# arduino_mega_shield.net
KiCad netlist of a schematic drawn in EAGLE
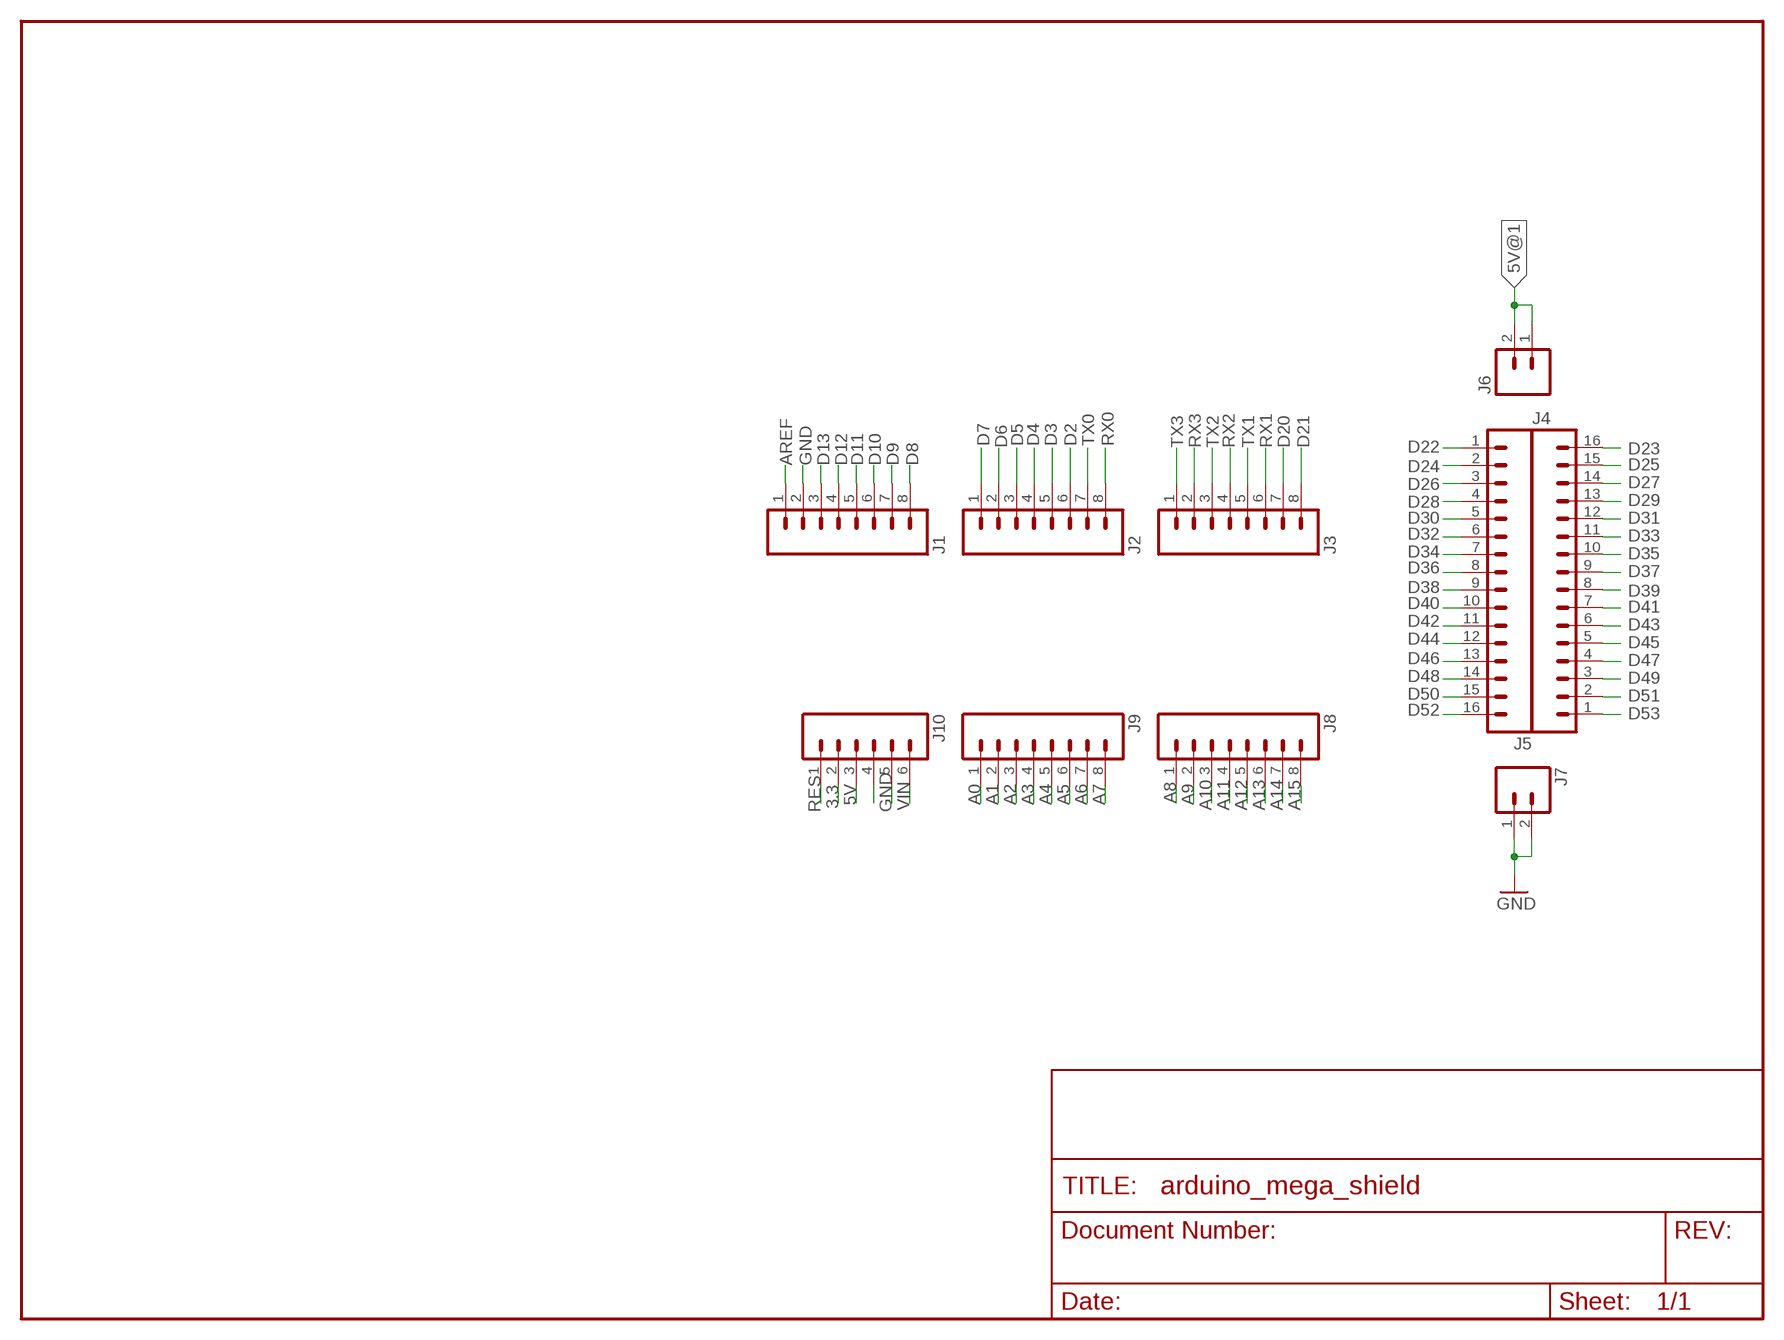
[diagram p0: schematic, sheet 1]

(export (version "E")
  (design (tool "Eeschema 10.0.6"))
  (components
    (comp (ref "J1")
      (value "M08LONGPADS")
      (footprint "eagle-import:1X08_LONGPADS")
      (libsource (lib "eagle-import") (part "M08LONGPADS"))
    )
    (comp (ref "J2")
      (value "M08LONGPADS")
      (footprint "eagle-import:1X08_LONGPADS")
      (libsource (lib "eagle-import") (part "M08LONGPADS"))
    )
    (comp (ref "J3")
      (value "M08LONGPADS")
      (footprint "eagle-import:1X08_LONGPADS")
      (libsource (lib "eagle-import") (part "M08LONGPADS"))
    )
    (comp (ref "J4")
      (value "M16PTH")
      (footprint "eagle-import:1X16")
      (libsource (lib "eagle-import") (part "M16PTH"))
    )
    (comp (ref "J5")
      (value "M16PTH")
      (footprint "eagle-import:1X16")
      (libsource (lib "eagle-import") (part "M16PTH"))
    )
    (comp (ref "J6")
      (value "M02PTH")
      (footprint "eagle-import:1X02")
      (libsource (lib "eagle-import") (part "M02PTH"))
    )
    (comp (ref "J7")
      (value "M02PTH")
      (footprint "eagle-import:1X02")
      (libsource (lib "eagle-import") (part "M02PTH"))
    )
    (comp (ref "J8")
      (value "M08LONGPADS")
      (footprint "eagle-import:1X08_LONGPADS")
      (libsource (lib "eagle-import") (part "M08LONGPADS"))
    )
    (comp (ref "J9")
      (value "M08LONGPADS")
      (footprint "eagle-import:1X08_LONGPADS")
      (libsource (lib "eagle-import") (part "M08LONGPADS"))
    )
    (comp (ref "J10")
      (value "M06LONGPADS")
      (footprint "eagle-import:1X06_LONGPADS")
      (libsource (lib "eagle-import") (part "M06LONGPADS"))
    )
  )
  (nets
    (net (code "1") (name "/3.3") (class "Default")
      (node (ref "J10") (pin "2") (pinfunction "2_2") (pintype "passive"))
    )
    (net (code "2") (name "/5V") (class "Default")
      (node (ref "J10") (pin "3") (pinfunction "3_3") (pintype "passive"))
    )
    (net (code "3") (name "/A0") (class "Default")
      (node (ref "J9") (pin "1") (pinfunction "1_1") (pintype "passive"))
    )
    (net (code "4") (name "/A1") (class "Default")
      (node (ref "J9") (pin "2") (pinfunction "2_2") (pintype "passive"))
    )
    (net (code "5") (name "/A2") (class "Default")
      (node (ref "J9") (pin "3") (pinfunction "3_3") (pintype "passive"))
    )
    (net (code "6") (name "/A3") (class "Default")
      (node (ref "J9") (pin "4") (pinfunction "4_4") (pintype "passive"))
    )
    (net (code "7") (name "/A4") (class "Default")
      (node (ref "J9") (pin "5") (pinfunction "5_5") (pintype "passive"))
    )
    (net (code "8") (name "/A5") (class "Default")
      (node (ref "J9") (pin "6") (pinfunction "6_6") (pintype "passive"))
    )
    (net (code "9") (name "/A6") (class "Default")
      (node (ref "J9") (pin "7") (pinfunction "7_7") (pintype "passive"))
    )
    (net (code "10") (name "/A7") (class "Default")
      (node (ref "J9") (pin "8") (pinfunction "8_8") (pintype "passive"))
    )
    (net (code "11") (name "/A8") (class "Default")
      (node (ref "J8") (pin "1") (pinfunction "1_1") (pintype "passive"))
    )
    (net (code "12") (name "/A9") (class "Default")
      (node (ref "J8") (pin "2") (pinfunction "2_2") (pintype "passive"))
    )
    (net (code "13") (name "/A10") (class "Default")
      (node (ref "J8") (pin "3") (pinfunction "3_3") (pintype "passive"))
    )
    (net (code "14") (name "/A11") (class "Default")
      (node (ref "J8") (pin "4") (pinfunction "4_4") (pintype "passive"))
    )
    (net (code "15") (name "/A12") (class "Default")
      (node (ref "J8") (pin "5") (pinfunction "5_5") (pintype "passive"))
    )
    (net (code "16") (name "/A13") (class "Default")
      (node (ref "J8") (pin "6") (pinfunction "6_6") (pintype "passive"))
    )
    (net (code "17") (name "/A14") (class "Default")
      (node (ref "J8") (pin "7") (pinfunction "7_7") (pintype "passive"))
    )
    (net (code "18") (name "/A15") (class "Default")
      (node (ref "J8") (pin "8") (pinfunction "8_8") (pintype "passive"))
    )
    (net (code "19") (name "/AREF") (class "Default")
      (node (ref "J1") (pin "1") (pinfunction "1_1") (pintype "passive"))
    )
    (net (code "20") (name "/D2") (class "Default")
      (node (ref "J2") (pin "6") (pinfunction "6_6") (pintype "passive"))
    )
    (net (code "21") (name "/D3") (class "Default")
      (node (ref "J2") (pin "5") (pinfunction "5_5") (pintype "passive"))
    )
    (net (code "22") (name "/D4") (class "Default")
      (node (ref "J2") (pin "4") (pinfunction "4_4") (pintype "passive"))
    )
    (net (code "23") (name "/D5") (class "Default")
      (node (ref "J2") (pin "3") (pinfunction "3_3") (pintype "passive"))
    )
    (net (code "24") (name "/D6") (class "Default")
      (node (ref "J2") (pin "2") (pinfunction "2_2") (pintype "passive"))
    )
    (net (code "25") (name "/D7") (class "Default")
      (node (ref "J2") (pin "1") (pinfunction "1_1") (pintype "passive"))
    )
    (net (code "26") (name "/D8") (class "Default")
      (node (ref "J1") (pin "8") (pinfunction "8_8") (pintype "passive"))
    )
    (net (code "27") (name "/D9") (class "Default")
      (node (ref "J1") (pin "7") (pinfunction "7_7") (pintype "passive"))
    )
    (net (code "28") (name "/D10") (class "Default")
      (node (ref "J1") (pin "6") (pinfunction "6_6") (pintype "passive"))
    )
    (net (code "29") (name "/D11") (class "Default")
      (node (ref "J1") (pin "5") (pinfunction "5_5") (pintype "passive"))
    )
    (net (code "30") (name "/D12") (class "Default")
      (node (ref "J1") (pin "4") (pinfunction "4_4") (pintype "passive"))
    )
    (net (code "31") (name "/D13") (class "Default")
      (node (ref "J1") (pin "3") (pinfunction "3_3") (pintype "passive"))
    )
    (net (code "32") (name "/D20") (class "Default")
      (node (ref "J3") (pin "7") (pinfunction "7_7") (pintype "passive"))
    )
    (net (code "33") (name "/D21") (class "Default")
      (node (ref "J3") (pin "8") (pinfunction "8_8") (pintype "passive"))
    )
    (net (code "34") (name "/D22") (class "Default")
      (node (ref "J5") (pin "1") (pinfunction "1_1") (pintype "passive"))
    )
    (net (code "35") (name "/D23") (class "Default")
      (node (ref "J4") (pin "16") (pinfunction "16_16") (pintype "passive"))
    )
    (net (code "36") (name "/D24") (class "Default")
      (node (ref "J5") (pin "2") (pinfunction "2_2") (pintype "passive"))
    )
    (net (code "37") (name "/D25") (class "Default")
      (node (ref "J4") (pin "15") (pinfunction "15_15") (pintype "passive"))
    )
    (net (code "38") (name "/D26") (class "Default")
      (node (ref "J5") (pin "3") (pinfunction "3_3") (pintype "passive"))
    )
    (net (code "39") (name "/D27") (class "Default")
      (node (ref "J4") (pin "14") (pinfunction "14_14") (pintype "passive"))
    )
    (net (code "40") (name "/D28") (class "Default")
      (node (ref "J5") (pin "4") (pinfunction "4_4") (pintype "passive"))
    )
    (net (code "41") (name "/D29") (class "Default")
      (node (ref "J4") (pin "13") (pinfunction "13_13") (pintype "passive"))
    )
    (net (code "42") (name "/D30") (class "Default")
      (node (ref "J5") (pin "5") (pinfunction "5_5") (pintype "passive"))
    )
    (net (code "43") (name "/D31") (class "Default")
      (node (ref "J4") (pin "12") (pinfunction "12_12") (pintype "passive"))
    )
    (net (code "44") (name "/D32") (class "Default")
      (node (ref "J5") (pin "6") (pinfunction "6_6") (pintype "passive"))
    )
    (net (code "45") (name "/D33") (class "Default")
      (node (ref "J4") (pin "11") (pinfunction "11_11") (pintype "passive"))
    )
    (net (code "46") (name "/D34") (class "Default")
      (node (ref "J5") (pin "7") (pinfunction "7_7") (pintype "passive"))
    )
    (net (code "47") (name "/D35") (class "Default")
      (node (ref "J4") (pin "10") (pinfunction "10_10") (pintype "passive"))
    )
    (net (code "48") (name "/D36") (class "Default")
      (node (ref "J5") (pin "8") (pinfunction "8_8") (pintype "passive"))
    )
    (net (code "49") (name "/D37") (class "Default")
      (node (ref "J4") (pin "9") (pinfunction "9_9") (pintype "passive"))
    )
    (net (code "50") (name "/D38") (class "Default")
      (node (ref "J5") (pin "9") (pinfunction "9_9") (pintype "passive"))
    )
    (net (code "51") (name "/D39") (class "Default")
      (node (ref "J4") (pin "8") (pinfunction "8_8") (pintype "passive"))
    )
    (net (code "52") (name "/D40") (class "Default")
      (node (ref "J5") (pin "10") (pinfunction "10_10") (pintype "passive"))
    )
    (net (code "53") (name "/D41") (class "Default")
      (node (ref "J4") (pin "7") (pinfunction "7_7") (pintype "passive"))
    )
    (net (code "54") (name "/D42") (class "Default")
      (node (ref "J5") (pin "11") (pinfunction "11_11") (pintype "passive"))
    )
    (net (code "55") (name "/D43") (class "Default")
      (node (ref "J4") (pin "6") (pinfunction "6_6") (pintype "passive"))
    )
    (net (code "56") (name "/D44") (class "Default")
      (node (ref "J5") (pin "12") (pinfunction "12_12") (pintype "passive"))
    )
    (net (code "57") (name "/D45") (class "Default")
      (node (ref "J4") (pin "5") (pinfunction "5_5") (pintype "passive"))
    )
    (net (code "58") (name "/D46") (class "Default")
      (node (ref "J5") (pin "13") (pinfunction "13_13") (pintype "passive"))
    )
    (net (code "59") (name "/D47") (class "Default")
      (node (ref "J4") (pin "4") (pinfunction "4_4") (pintype "passive"))
    )
    (net (code "60") (name "/D48") (class "Default")
      (node (ref "J5") (pin "14") (pinfunction "14_14") (pintype "passive"))
    )
    (net (code "61") (name "/D49") (class "Default")
      (node (ref "J4") (pin "3") (pinfunction "3_3") (pintype "passive"))
    )
    (net (code "62") (name "/D50") (class "Default")
      (node (ref "J5") (pin "15") (pinfunction "15_15") (pintype "passive"))
    )
    (net (code "63") (name "/D51") (class "Default")
      (node (ref "J4") (pin "2") (pinfunction "2_2") (pintype "passive"))
    )
    (net (code "64") (name "/D52") (class "Default")
      (node (ref "J5") (pin "16") (pinfunction "16_16") (pintype "passive"))
    )
    (net (code "65") (name "/D53") (class "Default")
      (node (ref "J4") (pin "1") (pinfunction "1_1") (pintype "passive"))
    )
    (net (code "66") (name "/RES") (class "Default")
      (node (ref "J10") (pin "1") (pinfunction "1_1") (pintype "passive"))
    )
    (net (code "67") (name "/RX0") (class "Default")
      (node (ref "J2") (pin "8") (pinfunction "8_8") (pintype "passive"))
    )
    (net (code "68") (name "/RX1") (class "Default")
      (node (ref "J3") (pin "6") (pinfunction "6_6") (pintype "passive"))
    )
    (net (code "69") (name "/RX2") (class "Default")
      (node (ref "J3") (pin "4") (pinfunction "4_4") (pintype "passive"))
    )
    (net (code "70") (name "/RX3") (class "Default")
      (node (ref "J3") (pin "2") (pinfunction "2_2") (pintype "passive"))
    )
    (net (code "71") (name "/TX0") (class "Default")
      (node (ref "J2") (pin "7") (pinfunction "7_7") (pintype "passive"))
    )
    (net (code "72") (name "/TX1") (class "Default")
      (node (ref "J3") (pin "5") (pinfunction "5_5") (pintype "passive"))
    )
    (net (code "73") (name "/TX2") (class "Default")
      (node (ref "J3") (pin "3") (pinfunction "3_3") (pintype "passive"))
    )
    (net (code "74") (name "/TX3") (class "Default")
      (node (ref "J3") (pin "1") (pinfunction "1_1") (pintype "passive"))
    )
    (net (code "75") (name "/VIN") (class "Default")
      (node (ref "J10") (pin "6") (pinfunction "6_6") (pintype "passive"))
    )
    (net (code "76") (name "5V@1") (class "Default")
      (node (ref "J6") (pin "1") (pinfunction "1_1") (pintype "passive"))
      (node (ref "J6") (pin "2") (pinfunction "2_2") (pintype "passive"))
    )
    (net (code "77") (name "GND") (class "Default")
      (node (ref "J1") (pin "2") (pinfunction "2_2") (pintype "passive"))
      (node (ref "J10") (pin "4") (pinfunction "4_4") (pintype "passive"))
      (node (ref "J10") (pin "5") (pinfunction "5_5") (pintype "passive"))
      (node (ref "J7") (pin "1") (pinfunction "1_1") (pintype "passive"))
      (node (ref "J7") (pin "2") (pinfunction "2_2") (pintype "passive"))
    )
  )
)
